# XMeter.net
KiCad netlist of a schematic drawn in Altium Designer
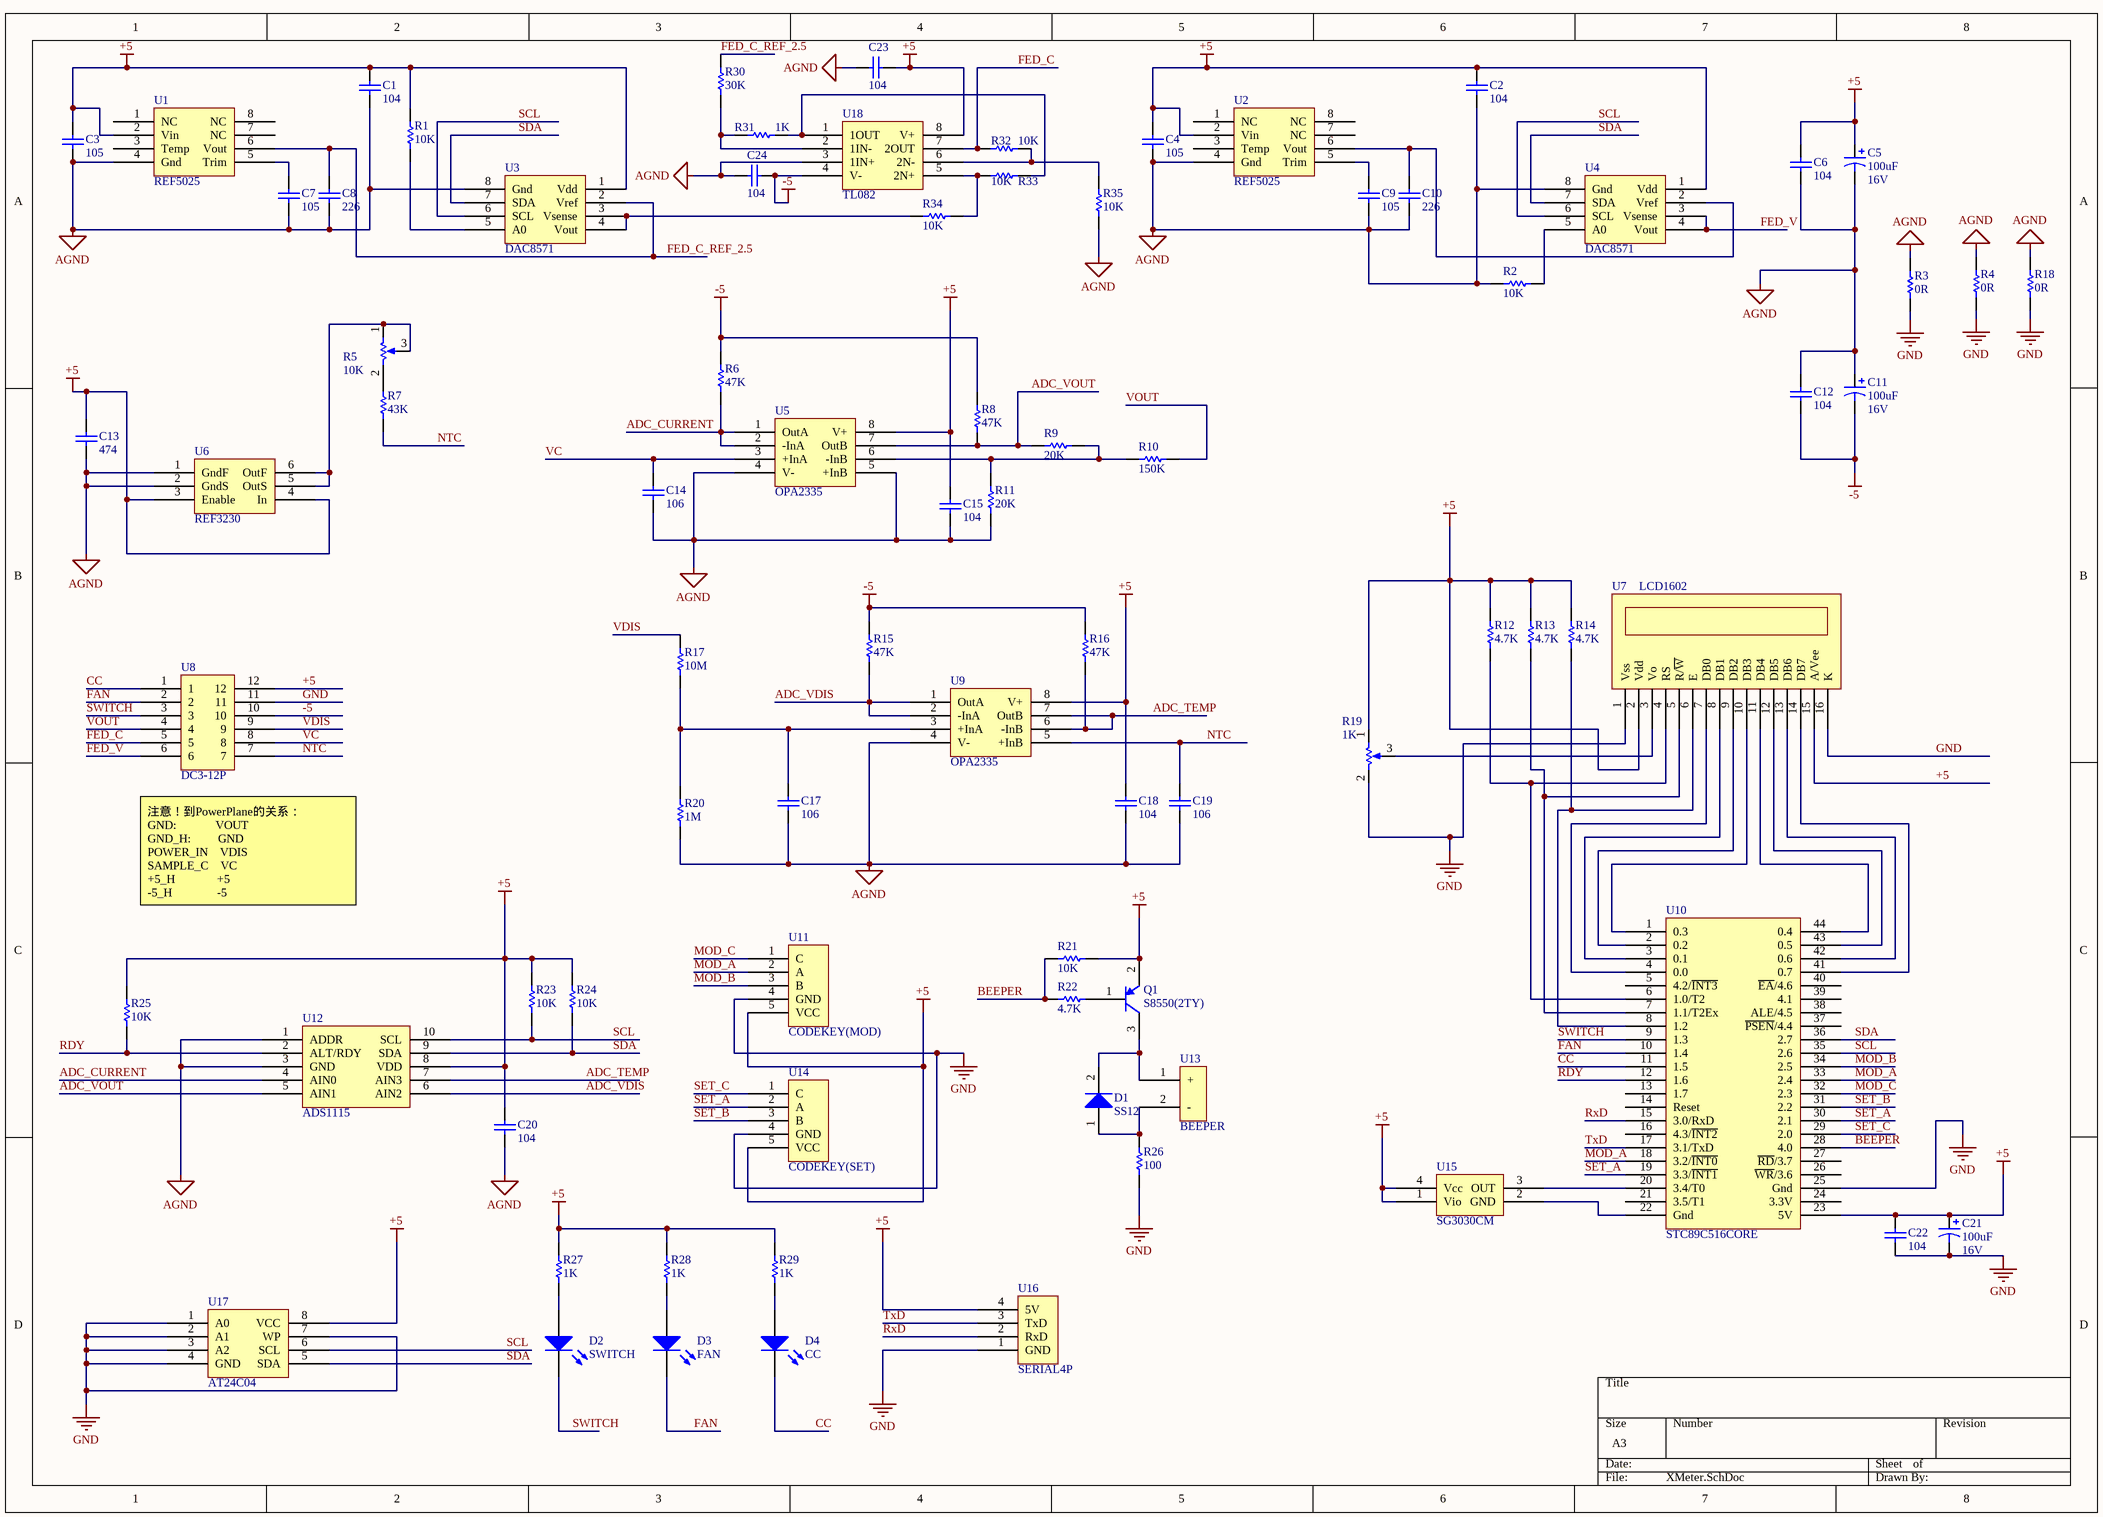
[diagram p0: XMeter.SchDoc]

(export (version "E")
  (design (tool "Eeschema 10.0.6"))
  (components
    (comp (ref "C1")
      (value "104")
      (footprint "CNCPowerSupply:CAPC1608L")
      (description "Capacitor")
      (fields (field (name "PUBLISHER") "Altium Limited"))
      (libsource (lib "Miscellaneous Devices") (part "Cap"))
    )
    (comp (ref "C2")
      (value "104")
      (footprint "CNCPowerSupply:CAPC1608L")
      (description "Capacitor")
      (fields (field (name "PUBLISHER") "Altium Limited"))
      (libsource (lib "Miscellaneous Devices") (part "Cap"))
    )
    (comp (ref "C3")
      (value "105")
      (footprint "CNCPowerSupply:CAPC1608L")
      (description "Capacitor")
      (fields (field (name "PUBLISHER") "Altium Limited"))
      (libsource (lib "Miscellaneous Devices") (part "Cap"))
    )
    (comp (ref "C4")
      (value "105")
      (footprint "CNCPowerSupply:CAPC1608L")
      (description "Capacitor")
      (fields (field (name "PUBLISHER") "Altium Limited"))
      (libsource (lib "Miscellaneous Devices") (part "Cap"))
    )
    (comp (ref "C5")
      (value "16V")
      (footprint "CNCPowerSupply:TC6032-2412")
      (description "Polarized Capacitor (Radial)")
      (fields (field (name "ALTIUM_VALUE") "100uF") (field (name "PUBLISHER") "Altium Limited"))
      (libsource (lib "Miscellaneous Devices") (part "Cap Pol1"))
    )
    (comp (ref "C6")
      (value "104")
      (footprint "CNCPowerSupply:CAPC1608L")
      (description "Capacitor")
      (fields (field (name "PUBLISHER") "Altium Limited"))
      (libsource (lib "Miscellaneous Devices") (part "Cap"))
    )
    (comp (ref "C7")
      (value "105")
      (footprint "CNCPowerSupply:CAPC1608L")
      (description "Capacitor")
      (fields (field (name "PUBLISHER") "Altium Limited"))
      (libsource (lib "Miscellaneous Devices") (part "Cap"))
    )
    (comp (ref "C8")
      (value "226")
      (footprint "CNCPowerSupply:C1206")
      (description "Capacitor")
      (fields (field (name "PUBLISHER") "Altium Limited"))
      (libsource (lib "Miscellaneous Devices") (part "Cap"))
    )
    (comp (ref "C9")
      (value "105")
      (footprint "CNCPowerSupply:CAPC1608L")
      (description "Capacitor")
      (fields (field (name "PUBLISHER") "Altium Limited"))
      (libsource (lib "Miscellaneous Devices") (part "Cap"))
    )
    (comp (ref "C10")
      (value "226")
      (footprint "CNCPowerSupply:C1206")
      (description "Capacitor")
      (fields (field (name "PUBLISHER") "Altium Limited"))
      (libsource (lib "Miscellaneous Devices") (part "Cap"))
    )
    (comp (ref "C11")
      (value "16V")
      (footprint "CNCPowerSupply:TC6032-2412")
      (description "Polarized Capacitor (Radial)")
      (fields (field (name "ALTIUM_VALUE") "100uF") (field (name "PUBLISHER") "Altium Limited"))
      (libsource (lib "Miscellaneous Devices") (part "Cap Pol1"))
    )
    (comp (ref "C12")
      (value "104")
      (footprint "CNCPowerSupply:CAPC1608L")
      (description "Capacitor")
      (fields (field (name "PUBLISHER") "Altium Limited"))
      (libsource (lib "Miscellaneous Devices") (part "Cap"))
    )
    (comp (ref "C13")
      (value "474")
      (footprint "CNCPowerSupply:CAPC1608L")
      (description "Capacitor")
      (fields (field (name "PUBLISHER") "Altium Limited"))
      (libsource (lib "Miscellaneous Devices") (part "Cap"))
    )
    (comp (ref "C14")
      (value "106")
      (footprint "CNCPowerSupply:CAPC1608L")
      (description "Capacitor")
      (fields (field (name "PUBLISHER") "Altium Limited"))
      (libsource (lib "Miscellaneous Devices") (part "Cap"))
    )
    (comp (ref "C15")
      (value "104")
      (footprint "CNCPowerSupply:CAPC1608L")
      (description "Capacitor")
      (fields (field (name "PUBLISHER") "Altium Limited"))
      (libsource (lib "Miscellaneous Devices") (part "Cap"))
    )
    (comp (ref "C17")
      (value "106")
      (footprint "CNCPowerSupply:CAPC1608L")
      (description "Capacitor")
      (fields (field (name "PUBLISHER") "Altium Limited"))
      (libsource (lib "Miscellaneous Devices") (part "Cap"))
    )
    (comp (ref "C18")
      (value "104")
      (footprint "CNCPowerSupply:CAPC1608L")
      (description "Capacitor")
      (fields (field (name "PUBLISHER") "Altium Limited"))
      (libsource (lib "Miscellaneous Devices") (part "Cap"))
    )
    (comp (ref "C19")
      (value "106")
      (footprint "CNCPowerSupply:CAPC1608L")
      (description "Capacitor")
      (fields (field (name "PUBLISHER") "Altium Limited"))
      (libsource (lib "Miscellaneous Devices") (part "Cap"))
    )
    (comp (ref "C20")
      (value "104")
      (footprint "CNCPowerSupply:CAPC1608L")
      (description "Capacitor")
      (fields (field (name "PUBLISHER") "Altium Limited"))
      (libsource (lib "Miscellaneous Devices") (part "Cap"))
    )
    (comp (ref "C21")
      (value "16V")
      (footprint "CNCPowerSupply:TC6032-2412")
      (description "Polarized Capacitor (Radial)")
      (fields (field (name "ALTIUM_VALUE") "100uF") (field (name "PUBLISHER") "Altium Limited"))
      (libsource (lib "Miscellaneous Devices") (part "Cap Pol1"))
    )
    (comp (ref "C22")
      (value "104")
      (footprint "CNCPowerSupply:CAPC1608L")
      (description "Capacitor")
      (fields (field (name "PUBLISHER") "Altium Limited"))
      (libsource (lib "Miscellaneous Devices") (part "Cap"))
    )
    (comp (ref "C23")
      (value "104")
      (footprint "CNCPowerSupply:CAPC1608L")
      (description "Capacitor")
      (fields (field (name "PUBLISHER") "Altium Limited"))
      (libsource (lib "Miscellaneous Devices") (part "Cap"))
    )
    (comp (ref "C24")
      (value "104")
      (footprint "CNCPowerSupply:CAPC1608L")
      (description "Capacitor")
      (fields (field (name "PUBLISHER") "Altium Limited"))
      (libsource (lib "Miscellaneous Devices") (part "Cap"))
    )
    (comp (ref "D1")
      (value "SS12")
      (footprint "CNCPowerSupply:DO214AC SMA")
      (description "1 Amp General Purpose Rectifier")
      (fields (field (name "PUBLISHER") "Altium Limited"))
      (libsource (lib "Miscellaneous Devices") (part "Diode 1N4007"))
    )
    (comp (ref "D2")
      (value "SWITCH")
      (footprint "CNCPowerSupply:LED")
      (description "Typical RED GaAs LED")
      (fields (field (name "PUBLISHER") "Altium Limited"))
      (libsource (lib "Miscellaneous Devices") (part "LED1"))
    )
    (comp (ref "D3")
      (value "FAN")
      (footprint "CNCPowerSupply:LED")
      (description "Typical RED GaAs LED")
      (fields (field (name "PUBLISHER") "Altium Limited"))
      (libsource (lib "Miscellaneous Devices") (part "LED1"))
    )
    (comp (ref "D4")
      (value "CC")
      (footprint "CNCPowerSupply:LED")
      (description "Typical RED GaAs LED")
      (fields (field (name "PUBLISHER") "Altium Limited"))
      (libsource (lib "Miscellaneous Devices") (part "LED1"))
    )
    (comp (ref "Q1")
      (value "S8550(2TY)")
      (footprint "CNCPowerSupply:SOT-23B_L")
      (description "PNP Bipolar Transistor")
      (fields (field (name "PUBLISHER") "Altium Limited"))
      (libsource (lib "Miscellaneous Devices") (part "PNP"))
    )
    (comp (ref "R1")
      (value "10K")
      (footprint "CNCPowerSupply:RESC1608L")
      (description "Resistor")
      (fields (field (name "PUBLISHER") "Altium Limited"))
      (libsource (lib "Miscellaneous Devices") (part "Res1"))
    )
    (comp (ref "R2")
      (value "10K")
      (footprint "CNCPowerSupply:RESC1608L")
      (description "Resistor")
      (fields (field (name "PUBLISHER") "Altium Limited"))
      (libsource (lib "Miscellaneous Devices") (part "Res1"))
    )
    (comp (ref "R3")
      (value "0R")
      (footprint "CNCPowerSupply:RESC1608L")
      (description "Resistor")
      (fields (field (name "PUBLISHER") "Altium Limited"))
      (libsource (lib "Miscellaneous Devices") (part "Res1"))
    )
    (comp (ref "R4")
      (value "0R")
      (footprint "CNCPowerSupply:RESC1608L")
      (description "Resistor")
      (fields (field (name "PUBLISHER") "Altium Limited"))
      (libsource (lib "Miscellaneous Devices") (part "Res1"))
    )
    (comp (ref "R5")
      (value "10K")
      (footprint "CNCPowerSupply:VR5")
      (description "Potentiometer")
      (fields (field (name "PUBLISHER") "Altium Limited"))
      (libsource (lib "Miscellaneous Devices") (part "RPot"))
    )
    (comp (ref "R6")
      (value "47K")
      (footprint "CNCPowerSupply:RESC1608L")
      (description "Resistor")
      (fields (field (name "PUBLISHER") "Altium Limited"))
      (libsource (lib "Miscellaneous Devices") (part "Res1"))
    )
    (comp (ref "R7")
      (value "43K")
      (footprint "CNCPowerSupply:RESC1608L")
      (description "Resistor")
      (fields (field (name "PUBLISHER") "Altium Limited"))
      (libsource (lib "Miscellaneous Devices") (part "Res1"))
    )
    (comp (ref "R8")
      (value "47K")
      (footprint "CNCPowerSupply:RESC1608L")
      (description "Resistor")
      (fields (field (name "PUBLISHER") "Altium Limited"))
      (libsource (lib "Miscellaneous Devices") (part "Res1"))
    )
    (comp (ref "R9")
      (value "20K")
      (footprint "CNCPowerSupply:RESC1608L")
      (description "Resistor")
      (fields (field (name "PUBLISHER") "Altium Limited"))
      (libsource (lib "Miscellaneous Devices") (part "Res1"))
    )
    (comp (ref "R10")
      (value "150K")
      (footprint "CNCPowerSupply:RESC1608L")
      (description "Resistor")
      (fields (field (name "PUBLISHER") "Altium Limited"))
      (libsource (lib "Miscellaneous Devices") (part "Res1"))
    )
    (comp (ref "R11")
      (value "20K")
      (footprint "CNCPowerSupply:RESC1608L")
      (description "Resistor")
      (fields (field (name "PUBLISHER") "Altium Limited"))
      (libsource (lib "Miscellaneous Devices") (part "Res1"))
    )
    (comp (ref "R12")
      (value "4.7K")
      (footprint "CNCPowerSupply:RESC1608L")
      (description "Resistor")
      (fields (field (name "PUBLISHER") "Altium Limited"))
      (libsource (lib "Miscellaneous Devices") (part "Res1"))
    )
    (comp (ref "R13")
      (value "4.7K")
      (footprint "CNCPowerSupply:RESC1608L")
      (description "Resistor")
      (fields (field (name "PUBLISHER") "Altium Limited"))
      (libsource (lib "Miscellaneous Devices") (part "Res1"))
    )
    (comp (ref "R14")
      (value "4.7K")
      (footprint "CNCPowerSupply:RESC1608L")
      (description "Resistor")
      (fields (field (name "PUBLISHER") "Altium Limited"))
      (libsource (lib "Miscellaneous Devices") (part "Res1"))
    )
    (comp (ref "R15")
      (value "47K")
      (footprint "CNCPowerSupply:RESC1608L")
      (description "Resistor")
      (fields (field (name "PUBLISHER") "Altium Limited"))
      (libsource (lib "Miscellaneous Devices") (part "Res1"))
    )
    (comp (ref "R16")
      (value "47K")
      (footprint "CNCPowerSupply:RESC1608L")
      (description "Resistor")
      (fields (field (name "PUBLISHER") "Altium Limited"))
      (libsource (lib "Miscellaneous Devices") (part "Res1"))
    )
    (comp (ref "R17")
      (value "10M")
      (footprint "CNCPowerSupply:RESC1608L")
      (description "Resistor")
      (fields (field (name "PUBLISHER") "Altium Limited"))
      (libsource (lib "Miscellaneous Devices") (part "Res1"))
    )
    (comp (ref "R18")
      (value "0R")
      (footprint "CNCPowerSupply:RESC1608L")
      (description "Resistor")
      (fields (field (name "PUBLISHER") "Altium Limited"))
      (libsource (lib "Miscellaneous Devices") (part "Res1"))
    )
    (comp (ref "R19")
      (value "1K")
      (footprint "CNCPowerSupply:VR4")
      (description "Potentiometer")
      (fields (field (name "PUBLISHER") "Altium Limited"))
      (libsource (lib "Miscellaneous Devices") (part "RPot"))
    )
    (comp (ref "R20")
      (value "1M")
      (footprint "CNCPowerSupply:RESC1608L")
      (description "Resistor")
      (fields (field (name "PUBLISHER") "Altium Limited"))
      (libsource (lib "Miscellaneous Devices") (part "Res1"))
    )
    (comp (ref "R21")
      (value "10K")
      (footprint "CNCPowerSupply:RESC1608L")
      (description "Resistor")
      (fields (field (name "PUBLISHER") "Altium Limited"))
      (libsource (lib "Miscellaneous Devices") (part "Res1"))
    )
    (comp (ref "R22")
      (value "4.7K")
      (footprint "CNCPowerSupply:RESC1608L")
      (description "Resistor")
      (fields (field (name "PUBLISHER") "Altium Limited"))
      (libsource (lib "Miscellaneous Devices") (part "Res1"))
    )
    (comp (ref "R23")
      (value "10K")
      (footprint "CNCPowerSupply:RESC1608L")
      (description "Resistor")
      (fields (field (name "PUBLISHER") "Altium Limited"))
      (libsource (lib "Miscellaneous Devices") (part "Res1"))
    )
    (comp (ref "R24")
      (value "10K")
      (footprint "CNCPowerSupply:RESC1608L")
      (description "Resistor")
      (fields (field (name "PUBLISHER") "Altium Limited"))
      (libsource (lib "Miscellaneous Devices") (part "Res1"))
    )
    (comp (ref "R25")
      (value "10K")
      (footprint "CNCPowerSupply:RESC1608L")
      (description "Resistor")
      (fields (field (name "PUBLISHER") "Altium Limited"))
      (libsource (lib "Miscellaneous Devices") (part "Res1"))
    )
    (comp (ref "R26")
      (value "100")
      (footprint "CNCPowerSupply:RESC1608L")
      (description "Resistor")
      (fields (field (name "PUBLISHER") "Altium Limited"))
      (libsource (lib "Miscellaneous Devices") (part "Res1"))
    )
    (comp (ref "R27")
      (value "1K")
      (footprint "CNCPowerSupply:RESC1608L")
      (description "Resistor")
      (fields (field (name "PUBLISHER") "Altium Limited"))
      (libsource (lib "Miscellaneous Devices") (part "Res1"))
    )
    (comp (ref "R28")
      (value "1K")
      (footprint "CNCPowerSupply:RESC1608L")
      (description "Resistor")
      (fields (field (name "PUBLISHER") "Altium Limited"))
      (libsource (lib "Miscellaneous Devices") (part "Res1"))
    )
    (comp (ref "R29")
      (value "1K")
      (footprint "CNCPowerSupply:RESC1608L")
      (description "Resistor")
      (fields (field (name "PUBLISHER") "Altium Limited"))
      (libsource (lib "Miscellaneous Devices") (part "Res1"))
    )
    (comp (ref "R30")
      (value "30K")
      (footprint "CNCPowerSupply:RESC1608L")
      (description "Resistor")
      (fields (field (name "PUBLISHER") "Altium Limited"))
      (libsource (lib "Miscellaneous Devices") (part "Res1"))
    )
    (comp (ref "R31")
      (value "1K")
      (footprint "CNCPowerSupply:RESC1608L")
      (description "Resistor")
      (fields (field (name "PUBLISHER") "Altium Limited"))
      (libsource (lib "Miscellaneous Devices") (part "Res1"))
    )
    (comp (ref "R32")
      (value "10K")
      (footprint "CNCPowerSupply:RESC1608L")
      (description "Resistor")
      (fields (field (name "PUBLISHER") "Altium Limited"))
      (libsource (lib "Miscellaneous Devices") (part "Res1"))
    )
    (comp (ref "R33")
      (value "10K")
      (footprint "CNCPowerSupply:RESC1608L")
      (description "Resistor")
      (fields (field (name "PUBLISHER") "Altium Limited"))
      (libsource (lib "Miscellaneous Devices") (part "Res1"))
    )
    (comp (ref "R34")
      (value "10K")
      (footprint "CNCPowerSupply:RESC1608L")
      (description "Resistor")
      (fields (field (name "PUBLISHER") "Altium Limited"))
      (libsource (lib "Miscellaneous Devices") (part "Res1"))
    )
    (comp (ref "R35")
      (value "10K")
      (footprint "CNCPowerSupply:RESC1608L")
      (description "Resistor")
      (fields (field (name "PUBLISHER") "Altium Limited"))
      (libsource (lib "Miscellaneous Devices") (part "Res1"))
    )
    (comp (ref "U1")
      (value "REF5025")
      (footprint "CNCPowerSupply:SOP127P636-8L")
      (libsource (lib "CNCPowerSupply") (part "REF5025"))
    )
    (comp (ref "U2")
      (value "REF5025")
      (footprint "CNCPowerSupply:SOP127P636-8L")
      (libsource (lib "CNCPowerSupply") (part "REF5025"))
    )
    (comp (ref "U3")
      (value "DAC8571")
      (footprint "CNCPowerSupply:TSOP65P490-8AL")
      (libsource (lib "CNCPowerSupply") (part "DAC8571"))
    )
    (comp (ref "U4")
      (value "DAC8571")
      (footprint "CNCPowerSupply:TSOP65P490-8AL")
      (libsource (lib "CNCPowerSupply") (part "DAC8571"))
    )
    (comp (ref "U5")
      (value "OPA2335")
      (footprint "CNCPowerSupply:SOP127P636-8L")
      (libsource (lib "CNCPowerSupply") (part "OPA2335"))
    )
    (comp (ref "U6")
      (value "REF3230")
      (footprint "CNCPowerSupply:SOT26A-6L")
      (libsource (lib "CNCPowerSupply") (part "REF3230"))
    )
    (comp (ref "U7")
      (value "LCD1602")
      (footprint "CNCPowerSupply:LCD1602")
      (libsource (lib "CNCPowerSupply") (part "LCD1602"))
    )
    (comp (ref "U8")
      (value "DC3-12P")
      (footprint "CNCPowerSupply:DC3-12P")
      (libsource (lib "CNCPowerSupply") (part "DC3-12P"))
    )
    (comp (ref "U9")
      (value "OPA2335")
      (footprint "CNCPowerSupply:SOP127P636-8L")
      (libsource (lib "CNCPowerSupply") (part "OPA2335"))
    )
    (comp (ref "U10")
      (value "STC89C516CORE")
      (footprint "CNCPowerSupply:STC89516CORE")
      (libsource (lib "CNCPowerSupply") (part "STC89C516CORE"))
    )
    (comp (ref "U11")
      (value "CODEKEY(MOD)")
      (footprint "CNCPowerSupply:CODEKEY")
      (description "CODEKEY")
      (libsource (lib "CNCPowerSupply") (part "CODEKEY"))
    )
    (comp (ref "U12")
      (value "ADS1115")
      (footprint "CNCPowerSupply:TSSOP50P490-10AL")
      (libsource (lib "CNCPowerSupply") (part "ADS1115"))
    )
    (comp (ref "U13")
      (value "BEEPER")
      (footprint "CNCPowerSupply:BEEPER")
      (libsource (lib "CNCPowerSupply") (part "BEEPER"))
    )
    (comp (ref "U14")
      (value "CODEKEY(SET)")
      (footprint "CNCPowerSupply:CODEKEY")
      (description "CODEKEY")
      (libsource (lib "CNCPowerSupply") (part "CODEKEY"))
    )
    (comp (ref "U15")
      (value "SG3030CM")
      (footprint "CNCPowerSupply:SG3030CM")
      (libsource (lib "CNCPowerSupply") (part "SG3030CM"))
    )
    (comp (ref "U16")
      (value "SERIAL4P")
      (footprint "CNCPowerSupply:X254-4P")
      (libsource (lib "CNCPowerSupply") (part "SERIAL4P"))
    )
    (comp (ref "U17")
      (value "AT24C04")
      (footprint "CNCPowerSupply:DIP-8")
      (libsource (lib "CNCPowerSupply") (part "AT24C04"))
    )
    (comp (ref "U18")
      (value "TL082")
      (footprint "CNCPowerSupply:DIP-8")
      (libsource (lib "CNCPowerSupply") (part "TL082"))
    )
  )
  (nets
    (net (code "1") (name "+5") (class "Default")
      (node (ref "C1") (pin "2") (pinfunction "2_2") (pintype "passive"))
      (node (ref "C13") (pin "2") (pinfunction "2_2") (pintype "passive"))
      (node (ref "C15") (pin "2") (pinfunction "2_2") (pintype "passive"))
      (node (ref "C18") (pin "2") (pinfunction "2_2") (pintype "passive"))
      (node (ref "C2") (pin "2") (pinfunction "2_2") (pintype "passive"))
      (node (ref "C20") (pin "2") (pinfunction "2_2") (pintype "passive"))
      (node (ref "C21") (pin "1") (pinfunction "1_1") (pintype "passive"))
      (node (ref "C22") (pin "2") (pinfunction "2_2") (pintype "passive"))
      (node (ref "C23") (pin "1") (pinfunction "1_1") (pintype "passive"))
      (node (ref "C3") (pin "2") (pinfunction "2_2") (pintype "passive"))
      (node (ref "C4") (pin "2") (pinfunction "2_2") (pintype "passive"))
      (node (ref "C5") (pin "1") (pinfunction "1_1") (pintype "passive"))
      (node (ref "C6") (pin "2") (pinfunction "2_2") (pintype "passive"))
      (node (ref "Q1") (pin "2") (pinfunction "E_2") (pintype "passive"))
      (node (ref "R1") (pin "1") (pinfunction "1_1") (pintype "passive"))
      (node (ref "R12") (pin "1") (pinfunction "1_1") (pintype "passive"))
      (node (ref "R13") (pin "1") (pinfunction "1_1") (pintype "passive"))
      (node (ref "R14") (pin "1") (pinfunction "1_1") (pintype "passive"))
      (node (ref "R19") (pin "1") (pinfunction "TOP_1") (pintype "passive"))
      (node (ref "R21") (pin "2") (pinfunction "2_2") (pintype "passive"))
      (node (ref "R23") (pin "1") (pinfunction "1_1") (pintype "passive"))
      (node (ref "R24") (pin "1") (pinfunction "1_1") (pintype "passive"))
      (node (ref "R25") (pin "1") (pinfunction "1_1") (pintype "passive"))
      (node (ref "R27") (pin "2") (pinfunction "2_2") (pintype "passive"))
      (node (ref "R28") (pin "2") (pinfunction "2_2") (pintype "passive"))
      (node (ref "R29") (pin "2") (pinfunction "2_2") (pintype "passive"))
      (node (ref "U1") (pin "2") (pinfunction "Vin_2") (pintype "passive"))
      (node (ref "U10") (pin "23") (pinfunction "5V_23") (pintype "passive"))
      (node (ref "U11") (pin "5") (pinfunction "VCC_5") (pintype "passive"))
      (node (ref "U12") (pin "8") (pinfunction "VDD_8") (pintype "passive"))
      (node (ref "U14") (pin "5") (pinfunction "VCC_5") (pintype "passive"))
      (node (ref "U15") (pin "1") (pinfunction "Vio_1") (pintype "passive"))
      (node (ref "U15") (pin "4") (pinfunction "Vcc_4") (pintype "passive"))
      (node (ref "U16") (pin "4") (pinfunction "5V_4") (pintype "passive"))
      (node (ref "U17") (pin "8") (pinfunction "VCC_8") (pintype "passive"))
      (node (ref "U18") (pin "8") (pinfunction "V+_8") (pintype "passive"))
      (node (ref "U2") (pin "2") (pinfunction "Vin_2") (pintype "passive"))
      (node (ref "U3") (pin "1") (pinfunction "Vdd_1") (pintype "passive"))
      (node (ref "U4") (pin "1") (pinfunction "Vdd_1") (pintype "passive"))
      (node (ref "U5") (pin "8") (pinfunction "V+_8") (pintype "passive"))
      (node (ref "U6") (pin "3") (pinfunction "Enable_3") (pintype "passive"))
      (node (ref "U6") (pin "4") (pinfunction "In_4") (pintype "passive"))
      (node (ref "U7") (pin "15") (pinfunction "A/Vee_15") (pintype "passive"))
      (node (ref "U7") (pin "2") (pinfunction "Vdd_2") (pintype "passive"))
      (node (ref "U8") (pin "12") (pinfunction "12_12") (pintype "passive"))
      (node (ref "U9") (pin "8") (pinfunction "V+_8") (pintype "passive"))
    )
    (net (code "2") (name "-5") (class "Default")
      (node (ref "C11") (pin "2") (pinfunction "2_2") (pintype "passive"))
      (node (ref "C12") (pin "1") (pinfunction "1_1") (pintype "passive"))
      (node (ref "C24") (pin "1") (pinfunction "1_1") (pintype "passive"))
      (node (ref "R15") (pin "1") (pinfunction "1_1") (pintype "passive"))
      (node (ref "R16") (pin "1") (pinfunction "1_1") (pintype "passive"))
      (node (ref "R6") (pin "1") (pinfunction "1_1") (pintype "passive"))
      (node (ref "R8") (pin "1") (pinfunction "1_1") (pintype "passive"))
      (node (ref "U18") (pin "4") (pinfunction "V-_4") (pintype "passive"))
      (node (ref "U8") (pin "10") (pinfunction "10_10") (pintype "passive"))
    )
    (net (code "3") (name "/ADC_CURRENT") (class "Default")
      (node (ref "R6") (pin "2") (pinfunction "2_2") (pintype "passive"))
      (node (ref "U12") (pin "4") (pinfunction "AIN0_4") (pintype "passive"))
      (node (ref "U5") (pin "1") (pinfunction "OutA_1") (pintype "passive"))
      (node (ref "U5") (pin "2") (pinfunction "-InA_2") (pintype "passive"))
    )
    (net (code "4") (name "/ADC_TEMP") (class "Default")
      (node (ref "R16") (pin "2") (pinfunction "2_2") (pintype "passive"))
      (node (ref "U12") (pin "7") (pinfunction "AIN3_7") (pintype "passive"))
      (node (ref "U9") (pin "6") (pinfunction "-InB_6") (pintype "passive"))
      (node (ref "U9") (pin "7") (pinfunction "OutB_7") (pintype "passive"))
    )
    (net (code "5") (name "/ADC_VDIS") (class "Default")
      (node (ref "R15") (pin "2") (pinfunction "2_2") (pintype "passive"))
      (node (ref "U12") (pin "6") (pinfunction "AIN2_6") (pintype "passive"))
      (node (ref "U9") (pin "1") (pinfunction "OutA_1") (pintype "passive"))
      (node (ref "U9") (pin "2") (pinfunction "-InA_2") (pintype "passive"))
    )
    (net (code "6") (name "/ADC_VOUT") (class "Default")
      (node (ref "R8") (pin "2") (pinfunction "2_2") (pintype "passive"))
      (node (ref "R9") (pin "1") (pinfunction "1_1") (pintype "passive"))
      (node (ref "U12") (pin "5") (pinfunction "AIN1_5") (pintype "passive"))
      (node (ref "U5") (pin "7") (pinfunction "OutB_7") (pintype "passive"))
    )
    (net (code "7") (name "/BEEPER") (class "Default")
      (node (ref "R21") (pin "1") (pinfunction "1_1") (pintype "passive"))
      (node (ref "R22") (pin "1") (pinfunction "1_1") (pintype "passive"))
      (node (ref "U10") (pin "28") (pinfunction "4.0_28") (pintype "passive"))
    )
    (net (code "8") (name "/CC") (class "Default")
      (node (ref "D4") (pin "2") (pinfunction "K_2") (pintype "passive"))
      (node (ref "U10") (pin "11") (pinfunction "1.5_11") (pintype "passive"))
      (node (ref "U8") (pin "1") (pinfunction "1_1") (pintype "passive"))
    )
    (net (code "9") (name "/FAN") (class "Default")
      (node (ref "D3") (pin "2") (pinfunction "K_2") (pintype "passive"))
      (node (ref "U10") (pin "10") (pinfunction "1.4_10") (pintype "passive"))
      (node (ref "U8") (pin "2") (pinfunction "2_2") (pintype "passive"))
    )
    (net (code "10") (name "/FED_C") (class "Default")
      (node (ref "R32") (pin "1") (pinfunction "1_1") (pintype "passive"))
      (node (ref "U18") (pin "7") (pinfunction "2OUT_7") (pintype "passive"))
      (node (ref "U8") (pin "5") (pinfunction "5_5") (pintype "passive"))
    )
    (net (code "11") (name "/FED_C_REF_2.5") (class "Default")
      (node (ref "C8") (pin "1") (pinfunction "1_1") (pintype "passive"))
      (node (ref "R30") (pin "2") (pinfunction "2_2") (pintype "passive"))
      (node (ref "U1") (pin "6") (pinfunction "Vout_6") (pintype "passive"))
      (node (ref "U3") (pin "2") (pinfunction "Vref_2") (pintype "passive"))
    )
    (net (code "12") (name "/FED_V") (class "Default")
      (node (ref "U4") (pin "3") (pinfunction "Vsense_3") (pintype "passive"))
      (node (ref "U4") (pin "4") (pinfunction "Vout_4") (pintype "passive"))
      (node (ref "U8") (pin "6") (pinfunction "6_6") (pintype "passive"))
    )
    (net (code "13") (name "/MOD_A") (class "Default")
      (node (ref "U10") (pin "18") (pinfunction "3.2/~{INT0}_18") (pintype "passive"))
      (node (ref "U10") (pin "33") (pinfunction "2.4_33") (pintype "passive"))
      (node (ref "U11") (pin "2") (pinfunction "A_2") (pintype "passive"))
    )
    (net (code "14") (name "/MOD_B") (class "Default")
      (node (ref "U10") (pin "34") (pinfunction "2.5_34") (pintype "passive"))
      (node (ref "U11") (pin "3") (pinfunction "B_3") (pintype "passive"))
    )
    (net (code "15") (name "/MOD_C") (class "Default")
      (node (ref "U10") (pin "32") (pinfunction "2.3_32") (pintype "passive"))
      (node (ref "U11") (pin "1") (pinfunction "C_1") (pintype "passive"))
    )
    (net (code "16") (name "/NTC") (class "Default")
      (node (ref "C19") (pin "2") (pinfunction "2_2") (pintype "passive"))
      (node (ref "R7") (pin "2") (pinfunction "2_2") (pintype "passive"))
      (node (ref "U8") (pin "7") (pinfunction "7_7") (pintype "passive"))
      (node (ref "U9") (pin "5") (pinfunction "+InB_5") (pintype "passive"))
    )
    (net (code "17") (name "/RDY") (class "Default")
      (node (ref "R25") (pin "2") (pinfunction "2_2") (pintype "passive"))
      (node (ref "U10") (pin "12") (pinfunction "1.6_12") (pintype "passive"))
      (node (ref "U12") (pin "2") (pinfunction "ALT/RDY_2") (pintype "passive"))
    )
    (net (code "18") (name "/RxD") (class "Default")
      (node (ref "U10") (pin "15") (pinfunction "3.0/RxD_15") (pintype "passive"))
      (node (ref "U16") (pin "2") (pinfunction "RxD_2") (pintype "passive"))
    )
    (net (code "19") (name "/SCL") (class "Default")
      (node (ref "R23") (pin "2") (pinfunction "2_2") (pintype "passive"))
      (node (ref "U10") (pin "35") (pinfunction "2.6_35") (pintype "passive"))
      (node (ref "U12") (pin "10") (pinfunction "SCL_10") (pintype "passive"))
      (node (ref "U17") (pin "6") (pinfunction "SCL_6") (pintype "passive"))
      (node (ref "U3") (pin "6") (pinfunction "SCL_6") (pintype "passive"))
      (node (ref "U4") (pin "6") (pinfunction "SCL_6") (pintype "passive"))
    )
    (net (code "20") (name "/SDA") (class "Default")
      (node (ref "R24") (pin "2") (pinfunction "2_2") (pintype "passive"))
      (node (ref "U10") (pin "36") (pinfunction "2.7_36") (pintype "passive"))
      (node (ref "U12") (pin "9") (pinfunction "SDA_9") (pintype "passive"))
      (node (ref "U17") (pin "5") (pinfunction "SDA_5") (pintype "passive"))
      (node (ref "U3") (pin "7") (pinfunction "SDA_7") (pintype "passive"))
      (node (ref "U4") (pin "7") (pinfunction "SDA_7") (pintype "passive"))
    )
    (net (code "21") (name "/SET_A") (class "Default")
      (node (ref "U10") (pin "19") (pinfunction "3.3/~{INT1}_19") (pintype "passive"))
      (node (ref "U10") (pin "30") (pinfunction "2.1_30") (pintype "passive"))
      (node (ref "U14") (pin "2") (pinfunction "A_2") (pintype "passive"))
    )
    (net (code "22") (name "/SET_B") (class "Default")
      (node (ref "U10") (pin "31") (pinfunction "2.2_31") (pintype "passive"))
      (node (ref "U14") (pin "3") (pinfunction "B_3") (pintype "passive"))
    )
    (net (code "23") (name "/SET_C") (class "Default")
      (node (ref "U10") (pin "29") (pinfunction "2.0_29") (pintype "passive"))
      (node (ref "U14") (pin "1") (pinfunction "C_1") (pintype "passive"))
    )
    (net (code "24") (name "/SWITCH") (class "Default")
      (node (ref "D2") (pin "2") (pinfunction "K_2") (pintype "passive"))
      (node (ref "U10") (pin "9") (pinfunction "1.3_9") (pintype "passive"))
      (node (ref "U8") (pin "3") (pinfunction "3_3") (pintype "passive"))
    )
    (net (code "25") (name "/TxD") (class "Default")
      (node (ref "U10") (pin "17") (pinfunction "3.1/TxD_17") (pintype "passive"))
      (node (ref "U16") (pin "3") (pinfunction "TxD_3") (pintype "passive"))
    )
    (net (code "26") (name "/VC") (class "Default")
      (node (ref "C14") (pin "2") (pinfunction "2_2") (pintype "passive"))
      (node (ref "U5") (pin "3") (pinfunction "+InA_3") (pintype "passive"))
      (node (ref "U8") (pin "8") (pinfunction "8_8") (pintype "passive"))
    )
    (net (code "27") (name "/VDIS") (class "Default")
      (node (ref "R17") (pin "1") (pinfunction "1_1") (pintype "passive"))
      (node (ref "U8") (pin "9") (pinfunction "9_9") (pintype "passive"))
    )
    (net (code "28") (name "/VOUT") (class "Default")
      (node (ref "R10") (pin "2") (pinfunction "2_2") (pintype "passive"))
      (node (ref "U8") (pin "4") (pinfunction "4_4") (pintype "passive"))
    )
    (net (code "29") (name "AGND") (class "Default")
      (node (ref "C1") (pin "1") (pinfunction "1_1") (pintype "passive"))
      (node (ref "C10") (pin "2") (pinfunction "2_2") (pintype "passive"))
      (node (ref "C11") (pin "1") (pinfunction "1_1") (pintype "passive"))
      (node (ref "C12") (pin "2") (pinfunction "2_2") (pintype "passive"))
      (node (ref "C13") (pin "1") (pinfunction "1_1") (pintype "passive"))
      (node (ref "C14") (pin "1") (pinfunction "1_1") (pintype "passive"))
      (node (ref "C15") (pin "1") (pinfunction "1_1") (pintype "passive"))
      (node (ref "C17") (pin "1") (pinfunction "1_1") (pintype "passive"))
      (node (ref "C18") (pin "1") (pinfunction "1_1") (pintype "passive"))
      (node (ref "C19") (pin "1") (pinfunction "1_1") (pintype "passive"))
      (node (ref "C2") (pin "1") (pinfunction "1_1") (pintype "passive"))
      (node (ref "C20") (pin "1") (pinfunction "1_1") (pintype "passive"))
      (node (ref "C23") (pin "2") (pinfunction "2_2") (pintype "passive"))
      (node (ref "C24") (pin "2") (pinfunction "2_2") (pintype "passive"))
      (node (ref "C3") (pin "1") (pinfunction "1_1") (pintype "passive"))
      (node (ref "C4") (pin "1") (pinfunction "1_1") (pintype "passive"))
      (node (ref "C5") (pin "2") (pinfunction "2_2") (pintype "passive"))
      (node (ref "C6") (pin "1") (pinfunction "1_1") (pintype "passive"))
      (node (ref "C7") (pin "1") (pinfunction "1_1") (pintype "passive"))
      (node (ref "C8") (pin "2") (pinfunction "2_2") (pintype "passive"))
      (node (ref "C9") (pin "1") (pinfunction "1_1") (pintype "passive"))
      (node (ref "R11") (pin "2") (pinfunction "2_2") (pintype "passive"))
      (node (ref "R18") (pin "1") (pinfunction "1_1") (pintype "passive"))
      (node (ref "R2") (pin "2") (pinfunction "2_2") (pintype "passive"))
      (node (ref "R20") (pin "2") (pinfunction "2_2") (pintype "passive"))
      (node (ref "R3") (pin "1") (pinfunction "1_1") (pintype "passive"))
      (node (ref "R35") (pin "2") (pinfunction "2_2") (pintype "passive"))
      (node (ref "R4") (pin "1") (pinfunction "1_1") (pintype "passive"))
      (node (ref "U1") (pin "4") (pinfunction "Gnd_4") (pintype "passive"))
      (node (ref "U12") (pin "1") (pinfunction "ADDR_1") (pintype "passive"))
      (node (ref "U12") (pin "3") (pinfunction "GND_3") (pintype "passive"))
      (node (ref "U18") (pin "3") (pinfunction "1IN+_3") (pintype "passive"))
      (node (ref "U2") (pin "4") (pinfunction "Gnd_4") (pintype "passive"))
      (node (ref "U3") (pin "8") (pinfunction "Gnd_8") (pintype "passive"))
      (node (ref "U4") (pin "8") (pinfunction "Gnd_8") (pintype "passive"))
      (node (ref "U5") (pin "4") (pinfunction "V-_4") (pintype "passive"))
      (node (ref "U5") (pin "5") (pinfunction "+InB_5") (pintype "passive"))
      (node (ref "U6") (pin "1") (pinfunction "GndF_1") (pintype "passive"))
      (node (ref "U6") (pin "2") (pinfunction "GndS_2") (pintype "passive"))
      (node (ref "U9") (pin "4") (pinfunction "V-_4") (pintype "passive"))
    )
    (net (code "30") (name "GND") (class "Default")
      (node (ref "C21") (pin "2") (pinfunction "2_2") (pintype "passive"))
      (node (ref "C22") (pin "1") (pinfunction "1_1") (pintype "passive"))
      (node (ref "R18") (pin "2") (pinfunction "2_2") (pintype "passive"))
      (node (ref "R19") (pin "2") (pinfunction "BOT_2") (pintype "passive"))
      (node (ref "R26") (pin "1") (pinfunction "1_1") (pintype "passive"))
      (node (ref "R3") (pin "2") (pinfunction "2_2") (pintype "passive"))
      (node (ref "R4") (pin "2") (pinfunction "2_2") (pintype "passive"))
      (node (ref "U10") (pin "25") (pinfunction "Gnd_25") (pintype "passive"))
      (node (ref "U11") (pin "4") (pinfunction "GND_4") (pintype "passive"))
      (node (ref "U14") (pin "4") (pinfunction "GND_4") (pintype "passive"))
      (node (ref "U16") (pin "1") (pinfunction "GND_1") (pintype "passive"))
      (node (ref "U17") (pin "1") (pinfunction "A0_1") (pintype "passive"))
      (node (ref "U17") (pin "2") (pinfunction "A1_2") (pintype "passive"))
      (node (ref "U17") (pin "3") (pinfunction "A2_3") (pintype "passive"))
      (node (ref "U17") (pin "4") (pinfunction "GND_4") (pintype "passive"))
      (node (ref "U17") (pin "7") (pinfunction "WP_7") (pintype "passive"))
      (node (ref "U7") (pin "1") (pinfunction "Vss_1") (pintype "passive"))
      (node (ref "U7") (pin "16") (pinfunction "K_16") (pintype "passive"))
      (node (ref "U8") (pin "11") (pinfunction "11_11") (pintype "passive"))
    )
    (net (code "31") (name "Net-(D1-A)") (class "Default")
      (node (ref "D1") (pin "1") (pinfunction "A_1") (pintype "passive"))
      (node (ref "R26") (pin "2") (pinfunction "2_2") (pintype "passive"))
      (node (ref "U13") (pin "2") (pinfunction "-_2") (pintype "passive"))
    )
    (net (code "32") (name "Net-(D1-K)") (class "Default")
      (node (ref "D1") (pin "2") (pinfunction "K_2") (pintype "passive"))
      (node (ref "Q1") (pin "3") (pinfunction "C_3") (pintype "passive"))
      (node (ref "U13") (pin "1") (pinfunction "+_1") (pintype "passive"))
    )
    (net (code "33") (name "Net-(D2-A)") (class "Default")
      (node (ref "D2") (pin "1") (pinfunction "A_1") (pintype "passive"))
      (node (ref "R27") (pin "1") (pinfunction "1_1") (pintype "passive"))
    )
    (net (code "34") (name "Net-(D3-A)") (class "Default")
      (node (ref "D3") (pin "1") (pinfunction "A_1") (pintype "passive"))
      (node (ref "R28") (pin "1") (pinfunction "1_1") (pintype "passive"))
    )
    (net (code "35") (name "Net-(D4-A)") (class "Default")
      (node (ref "D4") (pin "1") (pinfunction "A_1") (pintype "passive"))
      (node (ref "R29") (pin "1") (pinfunction "1_1") (pintype "passive"))
    )
    (net (code "36") (name "Net-(Q1-B)") (class "Default")
      (node (ref "Q1") (pin "1") (pinfunction "B_1") (pintype "passive"))
      (node (ref "R22") (pin "2") (pinfunction "2_2") (pintype "passive"))
    )
    (net (code "37") (name "Net-(R5-BOT)") (class "Default")
      (node (ref "R5") (pin "2") (pinfunction "BOT_2") (pintype "passive"))
      (node (ref "R7") (pin "1") (pinfunction "1_1") (pintype "passive"))
    )
    (net (code "38") (name "Net-(R5-TAP)") (class "Default")
      (node (ref "R5") (pin "1") (pinfunction "TOP_1") (pintype "passive"))
      (node (ref "R5") (pin "3") (pinfunction "TAP_3") (pintype "passive"))
      (node (ref "U6") (pin "5") (pinfunction "OutS_5") (pintype "passive"))
      (node (ref "U6") (pin "6") (pinfunction "OutF_6") (pintype "passive"))
    )
    (net (code "39") (name "Net-(R19-TAP)") (class "Default")
      (node (ref "R19") (pin "3") (pinfunction "TAP_3") (pintype "passive"))
      (node (ref "U7") (pin "3") (pinfunction "Vo_3") (pintype "passive"))
    )
    (net (code "40") (name "Net-(U1-Trim)") (class "Default")
      (node (ref "C7") (pin "2") (pinfunction "2_2") (pintype "passive"))
      (node (ref "U1") (pin "5") (pinfunction "Trim_5") (pintype "passive"))
    )
    (net (code "41") (name "Net-(U2-Trim)") (class "Default")
      (node (ref "C9") (pin "2") (pinfunction "2_2") (pintype "passive"))
      (node (ref "U2") (pin "5") (pinfunction "Trim_5") (pintype "passive"))
    )
    (net (code "42") (name "Net-(U2-Vout)") (class "Default")
      (node (ref "C10") (pin "1") (pinfunction "1_1") (pintype "passive"))
      (node (ref "U2") (pin "6") (pinfunction "Vout_6") (pintype "passive"))
      (node (ref "U4") (pin "2") (pinfunction "Vref_2") (pintype "passive"))
    )
    (net (code "43") (name "Net-(U3-A0)") (class "Default")
      (node (ref "R1") (pin "2") (pinfunction "2_2") (pintype "passive"))
      (node (ref "U3") (pin "5") (pinfunction "A0_5") (pintype "passive"))
    )
    (net (code "44") (name "Net-(U3-Vout)") (class "Default")
      (node (ref "R34") (pin "1") (pinfunction "1_1") (pintype "passive"))
      (node (ref "U3") (pin "3") (pinfunction "Vsense_3") (pintype "passive"))
      (node (ref "U3") (pin "4") (pinfunction "Vout_4") (pintype "passive"))
    )
    (net (code "45") (name "Net-(U4-A0)") (class "Default")
      (node (ref "R2") (pin "1") (pinfunction "1_1") (pintype "passive"))
      (node (ref "U4") (pin "5") (pinfunction "A0_5") (pintype "passive"))
    )
    (net (code "46") (name "Net-(U5--InB)") (class "Default")
      (node (ref "R10") (pin "1") (pinfunction "1_1") (pintype "passive"))
      (node (ref "R11") (pin "1") (pinfunction "1_1") (pintype "passive"))
      (node (ref "R9") (pin "2") (pinfunction "2_2") (pintype "passive"))
      (node (ref "U5") (pin "6") (pinfunction "-InB_6") (pintype "passive"))
    )
    (net (code "47") (name "Net-(U9-+InA)") (class "Default")
      (node (ref "C17") (pin "2") (pinfunction "2_2") (pintype "passive"))
      (node (ref "R17") (pin "2") (pinfunction "2_2") (pintype "passive"))
      (node (ref "R20") (pin "1") (pinfunction "1_1") (pintype "passive"))
      (node (ref "U9") (pin "3") (pinfunction "+InA_3") (pintype "passive"))
    )
    (net (code "48") (name "Net-(U10-0.0)") (class "Default")
      (node (ref "U10") (pin "4") (pinfunction "0.0_4") (pintype "passive"))
      (node (ref "U7") (pin "7") (pinfunction "DB0_7") (pintype "passive"))
    )
    (net (code "49") (name "Net-(U10-0.1)") (class "Default")
      (node (ref "U10") (pin "3") (pinfunction "0.1_3") (pintype "passive"))
      (node (ref "U7") (pin "8") (pinfunction "DB1_8") (pintype "passive"))
    )
    (net (code "50") (name "Net-(U10-0.2)") (class "Default")
      (node (ref "U10") (pin "2") (pinfunction "0.2_2") (pintype "passive"))
      (node (ref "U7") (pin "9") (pinfunction "DB2_9") (pintype "passive"))
    )
    (net (code "51") (name "Net-(U10-0.3)") (class "Default")
      (node (ref "U10") (pin "1") (pinfunction "0.3_1") (pintype "passive"))
      (node (ref "U7") (pin "10") (pinfunction "DB3_10") (pintype "passive"))
    )
    (net (code "52") (name "Net-(U10-0.4)") (class "Default")
      (node (ref "U10") (pin "44") (pinfunction "0.4_44") (pintype "passive"))
      (node (ref "U7") (pin "11") (pinfunction "DB4_11") (pintype "passive"))
    )
    (net (code "53") (name "Net-(U10-0.5)") (class "Default")
      (node (ref "U10") (pin "43") (pinfunction "0.5_43") (pintype "passive"))
      (node (ref "U7") (pin "12") (pinfunction "DB5_12") (pintype "passive"))
    )
    (net (code "54") (name "Net-(U10-0.6)") (class "Default")
      (node (ref "U10") (pin "42") (pinfunction "0.6_42") (pintype "passive"))
      (node (ref "U7") (pin "13") (pinfunction "DB6_13") (pintype "passive"))
    )
    (net (code "55") (name "Net-(U10-0.7)") (class "Default")
      (node (ref "U10") (pin "41") (pinfunction "0.7_41") (pintype "passive"))
      (node (ref "U7") (pin "14") (pinfunction "DB7_14") (pintype "passive"))
    )
    (net (code "56") (name "Net-(U10-1.0{slash}T2)") (class "Default")
      (node (ref "R12") (pin "2") (pinfunction "2_2") (pintype "passive"))
      (node (ref "U10") (pin "6") (pinfunction "1.0/T2_6") (pintype "passive"))
      (node (ref "U7") (pin "4") (pinfunction "RS_4") (pintype "passive"))
    )
    (net (code "57") (name "Net-(U10-1.1{slash}T2Ex)") (class "Default")
      (node (ref "R13") (pin "2") (pinfunction "2_2") (pintype "passive"))
      (node (ref "U10") (pin "7") (pinfunction "1.1/T2Ex_7") (pintype "passive"))
      (node (ref "U7") (pin "5") (pinfunction "R/~{W}_5") (pintype "passive"))
    )
    (net (code "58") (name "Net-(U10-1.2)") (class "Default")
      (node (ref "R14") (pin "2") (pinfunction "2_2") (pintype "passive"))
      (node (ref "U10") (pin "8") (pinfunction "1.2_8") (pintype "passive"))
      (node (ref "U7") (pin "6") (pinfunction "E_6") (pintype "passive"))
    )
    (net (code "59") (name "Net-(U10-3.4{slash}T0)") (class "Default")
      (node (ref "U10") (pin "20") (pinfunction "3.4/T0_20") (pintype "passive"))
      (node (ref "U15") (pin "3") (pinfunction "OUT_3") (pintype "passive"))
    )
    (net (code "60") (name "Net-(U15-GND)") (class "Default")
      (node (ref "U10") (pin "22") (pinfunction "Gnd_22") (pintype "passive"))
      (node (ref "U15") (pin "2") (pinfunction "GND_2") (pintype "passive"))
    )
    (net (code "61") (name "Net-(U18-1IN-)") (class "Default")
      (node (ref "R30") (pin "1") (pinfunction "1_1") (pintype "passive"))
      (node (ref "R31") (pin "1") (pinfunction "1_1") (pintype "passive"))
      (node (ref "U18") (pin "2") (pinfunction "1IN-_2") (pintype "passive"))
    )
    (net (code "62") (name "Net-(U18-1OUT)") (class "Default")
      (node (ref "R31") (pin "2") (pinfunction "2_2") (pintype "passive"))
      (node (ref "R33") (pin "2") (pinfunction "2_2") (pintype "passive"))
      (node (ref "U18") (pin "1") (pinfunction "1OUT_1") (pintype "passive"))
    )
    (net (code "63") (name "Net-(U18-2N+)") (class "Default")
      (node (ref "R33") (pin "1") (pinfunction "1_1") (pintype "passive"))
      (node (ref "R34") (pin "2") (pinfunction "2_2") (pintype "passive"))
      (node (ref "U18") (pin "5") (pinfunction "2N+_5") (pintype "passive"))
    )
    (net (code "64") (name "Net-(U18-2N-)") (class "Default")
      (node (ref "R32") (pin "2") (pinfunction "2_2") (pintype "passive"))
      (node (ref "R35") (pin "1") (pinfunction "1_1") (pintype "passive"))
      (node (ref "U18") (pin "6") (pinfunction "2N-_6") (pintype "passive"))
    )
    (net (code "65") (name "unconnected-(U1-NC-Pad1)") (class "Default")
      (node (ref "U1") (pin "1") (pinfunction "NC_1") (pintype "passive"))
    )
    (net (code "66") (name "unconnected-(U1-NC-Pad7)") (class "Default")
      (node (ref "U1") (pin "7") (pinfunction "NC_7") (pintype "passive"))
    )
    (net (code "67") (name "unconnected-(U1-NC-Pad8)") (class "Default")
      (node (ref "U1") (pin "8") (pinfunction "NC_8") (pintype "passive"))
    )
    (net (code "68") (name "unconnected-(U1-Temp-Pad3)") (class "Default")
      (node (ref "U1") (pin "3") (pinfunction "Temp_3") (pintype "passive"))
    )
    (net (code "69") (name "unconnected-(U2-NC-Pad1)") (class "Default")
      (node (ref "U2") (pin "1") (pinfunction "NC_1") (pintype "passive"))
    )
    (net (code "70") (name "unconnected-(U2-NC-Pad7)") (class "Default")
      (node (ref "U2") (pin "7") (pinfunction "NC_7") (pintype "passive"))
    )
    (net (code "71") (name "unconnected-(U2-NC-Pad8)") (class "Default")
      (node (ref "U2") (pin "8") (pinfunction "NC_8") (pintype "passive"))
    )
    (net (code "72") (name "unconnected-(U2-Temp-Pad3)") (class "Default")
      (node (ref "U2") (pin "3") (pinfunction "Temp_3") (pintype "passive"))
    )
    (net (code "73") (name "unconnected-(U10-1.7-Pad13)") (class "Default")
      (node (ref "U10") (pin "13") (pinfunction "1.7_13") (pintype "passive"))
    )
    (net (code "74") (name "unconnected-(U10-3.3V-Pad24)") (class "Default")
      (node (ref "U10") (pin "24") (pinfunction "3.3V_24") (pintype "passive"))
    )
    (net (code "75") (name "unconnected-(U10-3.5{slash}T1-Pad21)") (class "Default")
      (node (ref "U10") (pin "21") (pinfunction "3.5/T1_21") (pintype "passive"))
    )
    (net (code "76") (name "unconnected-(U10-4.1-Pad39)") (class "Default")
      (node (ref "U10") (pin "39") (pinfunction "4.1_39") (pintype "passive"))
    )
    (net (code "77") (name "unconnected-(U10-4.2{slash}~{INT3}-Pad5)") (class "Default")
      (node (ref "U10") (pin "5") (pinfunction "4.2/~{INT3}_5") (pintype "passive"))
    )
    (net (code "78") (name "unconnected-(U10-4.3{slash}~{INT2}-Pad16)") (class "Default")
      (node (ref "U10") (pin "16") (pinfunction "4.3/~{INT2}_16") (pintype "passive"))
    )
    (net (code "79") (name "unconnected-(U10-ALE{slash}4.5-Pad38)") (class "Default")
      (node (ref "U10") (pin "38") (pinfunction "ALE/4.5_38") (pintype "passive"))
    )
    (net (code "80") (name "unconnected-(U10-Reset-Pad14)") (class "Default")
      (node (ref "U10") (pin "14") (pinfunction "Reset_14") (pintype "passive"))
    )
    (net (code "81") (name "unconnected-(U10-~{EA}{slash}4.6-Pad40)") (class "Default")
      (node (ref "U10") (pin "40") (pinfunction "~{EA}/4.6_40") (pintype "passive"))
    )
    (net (code "82") (name "unconnected-(U10-~{PSEN}{slash}4.4-Pad37)") (class "Default")
      (node (ref "U10") (pin "37") (pinfunction "~{PSEN}/4.4_37") (pintype "passive"))
    )
    (net (code "83") (name "unconnected-(U10-~{RD}{slash}3.7-Pad27)") (class "Default")
      (node (ref "U10") (pin "27") (pinfunction "~{RD}/3.7_27") (pintype "passive"))
    )
    (net (code "84") (name "unconnected-(U10-~{WR}{slash}3.6-Pad26)") (class "Default")
      (node (ref "U10") (pin "26") (pinfunction "~{WR}/3.6_26") (pintype "passive"))
    )
  )
)
